# bldc_driver.net
KiCad netlist of a schematic drawn in EAGLE
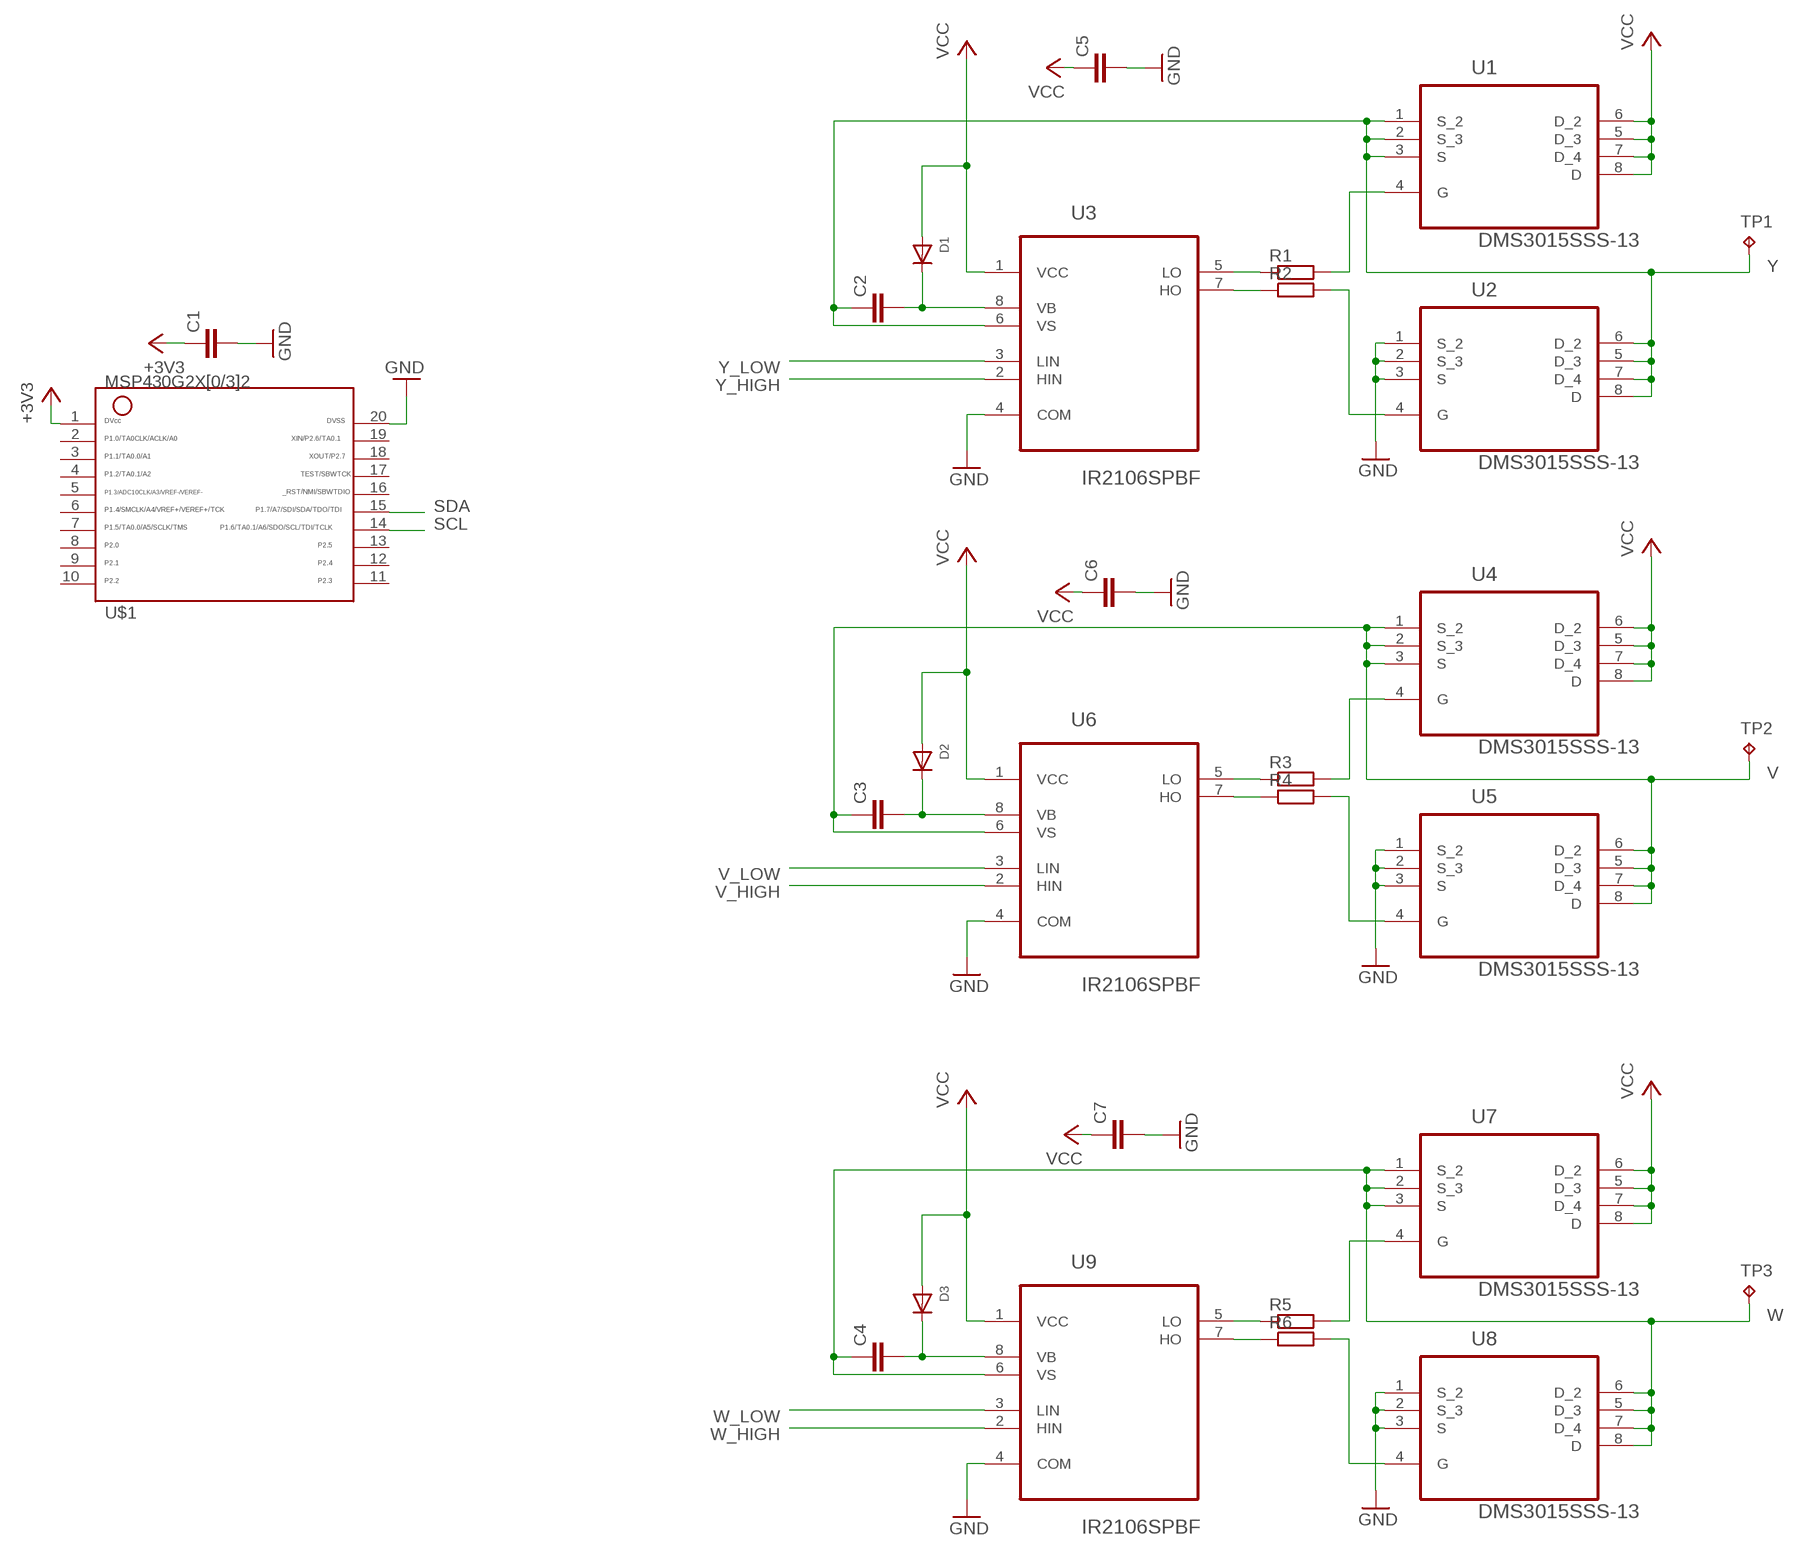
[diagram p0: schematic, sheet 1]

(export (version "E")
  (design (tool "Eeschema 10.0.6"))
  (components
    (comp (ref "C1")
      (value "C-EUC0805")
      (footprint "eagle-import:C0805")
      (libsource (lib "eagle-import") (part "C-EUC0805"))
    )
    (comp (ref "C2")
      (value "C-EUC0805")
      (footprint "eagle-import:C0805")
      (libsource (lib "eagle-import") (part "C-EUC0805"))
    )
    (comp (ref "C3")
      (value "C-EUC0805")
      (footprint "eagle-import:C0805")
      (libsource (lib "eagle-import") (part "C-EUC0805"))
    )
    (comp (ref "C4")
      (value "C-EUC0805")
      (footprint "eagle-import:C0805")
      (libsource (lib "eagle-import") (part "C-EUC0805"))
    )
    (comp (ref "C5")
      (value "C-EUC0805")
      (footprint "eagle-import:C0805")
      (libsource (lib "eagle-import") (part "C-EUC0805"))
    )
    (comp (ref "C6")
      (value "C-EUC0805")
      (footprint "eagle-import:C0805")
      (libsource (lib "eagle-import") (part "C-EUC0805"))
    )
    (comp (ref "C7")
      (value "C-EUC0805")
      (footprint "eagle-import:C0805")
      (libsource (lib "eagle-import") (part "C-EUC0805"))
    )
    (comp (ref "D1")
      (value "DIODE_SOD-123FL")
      (footprint "eagle-import:SOD-123FL")
      (libsource (lib "eagle-import") (part "DIODE_SOD-123FL"))
    )
    (comp (ref "D2")
      (value "DIODE_SOD-123FL")
      (footprint "eagle-import:SOD-123FL")
      (libsource (lib "eagle-import") (part "DIODE_SOD-123FL"))
    )
    (comp (ref "D3")
      (value "DIODE_SOD-123FL")
      (footprint "eagle-import:SOD-123FL")
      (libsource (lib "eagle-import") (part "DIODE_SOD-123FL"))
    )
    (comp (ref "R1")
      (value "R-EU_M0805")
      (footprint "eagle-import:M0805")
      (libsource (lib "eagle-import") (part "R-EU_M0805"))
    )
    (comp (ref "R2")
      (value "R-EU_M0805")
      (footprint "eagle-import:M0805")
      (libsource (lib "eagle-import") (part "R-EU_M0805"))
    )
    (comp (ref "R3")
      (value "R-EU_M0805")
      (footprint "eagle-import:M0805")
      (libsource (lib "eagle-import") (part "R-EU_M0805"))
    )
    (comp (ref "R4")
      (value "R-EU_M0805")
      (footprint "eagle-import:M0805")
      (libsource (lib "eagle-import") (part "R-EU_M0805"))
    )
    (comp (ref "R5")
      (value "R-EU_M0805")
      (footprint "eagle-import:M0805")
      (libsource (lib "eagle-import") (part "R-EU_M0805"))
    )
    (comp (ref "R6")
      (value "R-EU_M0805")
      (footprint "eagle-import:M0805")
      (libsource (lib "eagle-import") (part "R-EU_M0805"))
    )
    (comp (ref "TP1")
      (value "TPTP18R")
      (footprint "eagle-import:TP18R")
      (libsource (lib "eagle-import") (part "TPTP18R"))
    )
    (comp (ref "TP2")
      (value "TPTP18R")
      (footprint "eagle-import:TP18R")
      (libsource (lib "eagle-import") (part "TPTP18R"))
    )
    (comp (ref "TP3")
      (value "TPTP18R")
      (footprint "eagle-import:TP18R")
      (libsource (lib "eagle-import") (part "TPTP18R"))
    )
    (comp (ref "U$1")
      (value "G2X[0/3]2---PW20")
      (footprint "eagle-import:PW20")
      (libsource (lib "eagle-import") (part "G2X[0/3]2---PW20"))
    )
    (comp (ref "U1")
      (value "DMS3015SSS-13")
      (footprint "eagle-import:SOIC127P600X175-8N")
      (libsource (lib "eagle-import") (part "DMS3015SSS-13"))
    )
    (comp (ref "U2")
      (value "DMS3015SSS-13")
      (footprint "eagle-import:SOIC127P600X175-8N")
      (libsource (lib "eagle-import") (part "DMS3015SSS-13"))
    )
    (comp (ref "U3")
      (value "IR2106SPBF")
      (footprint "eagle-import:SOIC127P600X175-8N")
      (libsource (lib "eagle-import") (part "IR2106SPBF"))
    )
    (comp (ref "U4")
      (value "DMS3015SSS-13")
      (footprint "eagle-import:SOIC127P600X175-8N")
      (libsource (lib "eagle-import") (part "DMS3015SSS-13"))
    )
    (comp (ref "U5")
      (value "DMS3015SSS-13")
      (footprint "eagle-import:SOIC127P600X175-8N")
      (libsource (lib "eagle-import") (part "DMS3015SSS-13"))
    )
    (comp (ref "U6")
      (value "IR2106SPBF")
      (footprint "eagle-import:SOIC127P600X175-8N")
      (libsource (lib "eagle-import") (part "IR2106SPBF"))
    )
    (comp (ref "U7")
      (value "DMS3015SSS-13")
      (footprint "eagle-import:SOIC127P600X175-8N")
      (libsource (lib "eagle-import") (part "DMS3015SSS-13"))
    )
    (comp (ref "U8")
      (value "DMS3015SSS-13")
      (footprint "eagle-import:SOIC127P600X175-8N")
      (libsource (lib "eagle-import") (part "DMS3015SSS-13"))
    )
    (comp (ref "U9")
      (value "IR2106SPBF")
      (footprint "eagle-import:SOIC127P600X175-8N")
      (libsource (lib "eagle-import") (part "IR2106SPBF"))
    )
  )
  (nets
    (net (code "1") (name "+3V3") (class "Default")
      (node (ref "C1") (pin "1") (pinfunction "1_1") (pintype "passive"))
      (node (ref "U$1") (pin "1") (pinfunction "1_1") (pintype "bidirectional"))
    )
    (net (code "2") (name "/SCL") (class "Default")
      (node (ref "U$1") (pin "14") (pinfunction "14_14") (pintype "bidirectional"))
    )
    (net (code "3") (name "/SDA") (class "Default")
      (node (ref "U$1") (pin "15") (pinfunction "15_15") (pintype "bidirectional"))
    )
    (net (code "4") (name "/V") (class "Default")
      (node (ref "C3") (pin "1") (pinfunction "1_1") (pintype "passive"))
      (node (ref "TP2") (pin "TP") (pinfunction "TP_TP") (pintype "input"))
      (node (ref "U4") (pin "1") (pinfunction "S_2_1") (pintype "passive"))
      (node (ref "U4") (pin "2") (pinfunction "S_3_2") (pintype "passive"))
      (node (ref "U4") (pin "3") (pinfunction "S_3") (pintype "passive"))
      (node (ref "U5") (pin "5") (pinfunction "D_3_5") (pintype "passive"))
      (node (ref "U5") (pin "6") (pinfunction "D_2_6") (pintype "passive"))
      (node (ref "U5") (pin "7") (pinfunction "D_4_7") (pintype "passive"))
      (node (ref "U5") (pin "8") (pinfunction "D_8") (pintype "passive"))
      (node (ref "U6") (pin "6") (pinfunction "VS_6") (pintype "power_in"))
    )
    (net (code "5") (name "/V_HIGH") (class "Default")
      (node (ref "U6") (pin "2") (pinfunction "HIN_2") (pintype "input"))
    )
    (net (code "6") (name "/V_LOW") (class "Default")
      (node (ref "U6") (pin "3") (pinfunction "LIN_3") (pintype "input"))
    )
    (net (code "7") (name "/W") (class "Default")
      (node (ref "C4") (pin "1") (pinfunction "1_1") (pintype "passive"))
      (node (ref "TP3") (pin "TP") (pinfunction "TP_TP") (pintype "input"))
      (node (ref "U7") (pin "1") (pinfunction "S_2_1") (pintype "passive"))
      (node (ref "U7") (pin "2") (pinfunction "S_3_2") (pintype "passive"))
      (node (ref "U7") (pin "3") (pinfunction "S_3") (pintype "passive"))
      (node (ref "U8") (pin "5") (pinfunction "D_3_5") (pintype "passive"))
      (node (ref "U8") (pin "6") (pinfunction "D_2_6") (pintype "passive"))
      (node (ref "U8") (pin "7") (pinfunction "D_4_7") (pintype "passive"))
      (node (ref "U8") (pin "8") (pinfunction "D_8") (pintype "passive"))
      (node (ref "U9") (pin "6") (pinfunction "VS_6") (pintype "power_in"))
    )
    (net (code "8") (name "/W_HIGH") (class "Default")
      (node (ref "U9") (pin "2") (pinfunction "HIN_2") (pintype "input"))
    )
    (net (code "9") (name "/W_LOW") (class "Default")
      (node (ref "U9") (pin "3") (pinfunction "LIN_3") (pintype "input"))
    )
    (net (code "10") (name "/Y") (class "Default")
      (node (ref "C2") (pin "1") (pinfunction "1_1") (pintype "passive"))
      (node (ref "TP1") (pin "TP") (pinfunction "TP_TP") (pintype "input"))
      (node (ref "U1") (pin "1") (pinfunction "S_2_1") (pintype "passive"))
      (node (ref "U1") (pin "2") (pinfunction "S_3_2") (pintype "passive"))
      (node (ref "U1") (pin "3") (pinfunction "S_3") (pintype "passive"))
      (node (ref "U2") (pin "5") (pinfunction "D_3_5") (pintype "passive"))
      (node (ref "U2") (pin "6") (pinfunction "D_2_6") (pintype "passive"))
      (node (ref "U2") (pin "7") (pinfunction "D_4_7") (pintype "passive"))
      (node (ref "U2") (pin "8") (pinfunction "D_8") (pintype "passive"))
      (node (ref "U3") (pin "6") (pinfunction "VS_6") (pintype "power_in"))
    )
    (net (code "11") (name "/Y_HIGH") (class "Default")
      (node (ref "U3") (pin "2") (pinfunction "HIN_2") (pintype "input"))
    )
    (net (code "12") (name "/Y_LOW") (class "Default")
      (node (ref "U3") (pin "3") (pinfunction "LIN_3") (pintype "input"))
    )
    (net (code "13") (name "GND") (class "Default")
      (node (ref "C1") (pin "2") (pinfunction "2_2") (pintype "passive"))
      (node (ref "C5") (pin "2") (pinfunction "2_2") (pintype "passive"))
      (node (ref "C6") (pin "2") (pinfunction "2_2") (pintype "passive"))
      (node (ref "C7") (pin "2") (pinfunction "2_2") (pintype "passive"))
      (node (ref "U$1") (pin "20") (pinfunction "20_20") (pintype "bidirectional"))
      (node (ref "U2") (pin "1") (pinfunction "S_2_1") (pintype "passive"))
      (node (ref "U2") (pin "2") (pinfunction "S_3_2") (pintype "passive"))
      (node (ref "U2") (pin "3") (pinfunction "S_3") (pintype "passive"))
      (node (ref "U3") (pin "4") (pinfunction "COM_4") (pintype "passive"))
      (node (ref "U5") (pin "1") (pinfunction "S_2_1") (pintype "passive"))
      (node (ref "U5") (pin "2") (pinfunction "S_3_2") (pintype "passive"))
      (node (ref "U5") (pin "3") (pinfunction "S_3") (pintype "passive"))
      (node (ref "U6") (pin "4") (pinfunction "COM_4") (pintype "passive"))
      (node (ref "U8") (pin "1") (pinfunction "S_2_1") (pintype "passive"))
      (node (ref "U8") (pin "2") (pinfunction "S_3_2") (pintype "passive"))
      (node (ref "U8") (pin "3") (pinfunction "S_3") (pintype "passive"))
      (node (ref "U9") (pin "4") (pinfunction "COM_4") (pintype "passive"))
    )
    (net (code "14") (name "Net-(U1-G)") (class "Default")
      (node (ref "R1") (pin "2") (pinfunction "2_2") (pintype "passive"))
      (node (ref "U1") (pin "4") (pinfunction "G_4") (pintype "passive"))
    )
    (net (code "15") (name "Net-(U2-G)") (class "Default")
      (node (ref "R2") (pin "2") (pinfunction "2_2") (pintype "passive"))
      (node (ref "U2") (pin "4") (pinfunction "G_4") (pintype "passive"))
    )
    (net (code "16") (name "Net-(U3-HO)") (class "Default")
      (node (ref "R2") (pin "1") (pinfunction "1_1") (pintype "passive"))
      (node (ref "U3") (pin "7") (pinfunction "HO_7") (pintype "output"))
    )
    (net (code "17") (name "Net-(U3-LO)") (class "Default")
      (node (ref "R1") (pin "1") (pinfunction "1_1") (pintype "passive"))
      (node (ref "U3") (pin "5") (pinfunction "LO_5") (pintype "output"))
    )
    (net (code "18") (name "Net-(U3-VB)") (class "Default")
      (node (ref "C2") (pin "2") (pinfunction "2_2") (pintype "passive"))
      (node (ref "D1") (pin "C") (pinfunction "C_C") (pintype "passive"))
      (node (ref "U3") (pin "8") (pinfunction "VB_8") (pintype "power_in"))
    )
    (net (code "19") (name "Net-(U4-G)") (class "Default")
      (node (ref "R3") (pin "2") (pinfunction "2_2") (pintype "passive"))
      (node (ref "U4") (pin "4") (pinfunction "G_4") (pintype "passive"))
    )
    (net (code "20") (name "Net-(U5-G)") (class "Default")
      (node (ref "R4") (pin "2") (pinfunction "2_2") (pintype "passive"))
      (node (ref "U5") (pin "4") (pinfunction "G_4") (pintype "passive"))
    )
    (net (code "21") (name "Net-(U6-HO)") (class "Default")
      (node (ref "R4") (pin "1") (pinfunction "1_1") (pintype "passive"))
      (node (ref "U6") (pin "7") (pinfunction "HO_7") (pintype "output"))
    )
    (net (code "22") (name "Net-(U6-LO)") (class "Default")
      (node (ref "R3") (pin "1") (pinfunction "1_1") (pintype "passive"))
      (node (ref "U6") (pin "5") (pinfunction "LO_5") (pintype "output"))
    )
    (net (code "23") (name "Net-(U6-VB)") (class "Default")
      (node (ref "C3") (pin "2") (pinfunction "2_2") (pintype "passive"))
      (node (ref "D2") (pin "C") (pinfunction "C_C") (pintype "passive"))
      (node (ref "U6") (pin "8") (pinfunction "VB_8") (pintype "power_in"))
    )
    (net (code "24") (name "Net-(U7-G)") (class "Default")
      (node (ref "R5") (pin "2") (pinfunction "2_2") (pintype "passive"))
      (node (ref "U7") (pin "4") (pinfunction "G_4") (pintype "passive"))
    )
    (net (code "25") (name "Net-(U8-G)") (class "Default")
      (node (ref "R6") (pin "2") (pinfunction "2_2") (pintype "passive"))
      (node (ref "U8") (pin "4") (pinfunction "G_4") (pintype "passive"))
    )
    (net (code "26") (name "Net-(U9-HO)") (class "Default")
      (node (ref "R6") (pin "1") (pinfunction "1_1") (pintype "passive"))
      (node (ref "U9") (pin "7") (pinfunction "HO_7") (pintype "output"))
    )
    (net (code "27") (name "Net-(U9-LO)") (class "Default")
      (node (ref "R5") (pin "1") (pinfunction "1_1") (pintype "passive"))
      (node (ref "U9") (pin "5") (pinfunction "LO_5") (pintype "output"))
    )
    (net (code "28") (name "Net-(U9-VB)") (class "Default")
      (node (ref "C4") (pin "2") (pinfunction "2_2") (pintype "passive"))
      (node (ref "D3") (pin "C") (pinfunction "C_C") (pintype "passive"))
      (node (ref "U9") (pin "8") (pinfunction "VB_8") (pintype "power_in"))
    )
    (net (code "29") (name "VCC") (class "Default")
      (node (ref "C5") (pin "1") (pinfunction "1_1") (pintype "passive"))
      (node (ref "C6") (pin "1") (pinfunction "1_1") (pintype "passive"))
      (node (ref "C7") (pin "1") (pinfunction "1_1") (pintype "passive"))
      (node (ref "D1") (pin "A") (pinfunction "A_A") (pintype "passive"))
      (node (ref "D2") (pin "A") (pinfunction "A_A") (pintype "passive"))
      (node (ref "D3") (pin "A") (pinfunction "A_A") (pintype "passive"))
      (node (ref "U1") (pin "5") (pinfunction "D_3_5") (pintype "passive"))
      (node (ref "U1") (pin "6") (pinfunction "D_2_6") (pintype "passive"))
      (node (ref "U1") (pin "7") (pinfunction "D_4_7") (pintype "passive"))
      (node (ref "U1") (pin "8") (pinfunction "D_8") (pintype "passive"))
      (node (ref "U3") (pin "1") (pinfunction "VCC_1") (pintype "power_in"))
      (node (ref "U4") (pin "5") (pinfunction "D_3_5") (pintype "passive"))
      (node (ref "U4") (pin "6") (pinfunction "D_2_6") (pintype "passive"))
      (node (ref "U4") (pin "7") (pinfunction "D_4_7") (pintype "passive"))
      (node (ref "U4") (pin "8") (pinfunction "D_8") (pintype "passive"))
      (node (ref "U6") (pin "1") (pinfunction "VCC_1") (pintype "power_in"))
      (node (ref "U7") (pin "5") (pinfunction "D_3_5") (pintype "passive"))
      (node (ref "U7") (pin "6") (pinfunction "D_2_6") (pintype "passive"))
      (node (ref "U7") (pin "7") (pinfunction "D_4_7") (pintype "passive"))
      (node (ref "U7") (pin "8") (pinfunction "D_8") (pintype "passive"))
      (node (ref "U9") (pin "1") (pinfunction "VCC_1") (pintype "power_in"))
    )
    (net (code "30") (name "unconnected-(U$1-Pad2)") (class "Default")
      (node (ref "U$1") (pin "2") (pinfunction "2_2") (pintype "bidirectional"))
    )
    (net (code "31") (name "unconnected-(U$1-Pad3)") (class "Default")
      (node (ref "U$1") (pin "3") (pinfunction "3_3") (pintype "bidirectional"))
    )
    (net (code "32") (name "unconnected-(U$1-Pad4)") (class "Default")
      (node (ref "U$1") (pin "4") (pinfunction "4_4") (pintype "bidirectional"))
    )
    (net (code "33") (name "unconnected-(U$1-Pad5)") (class "Default")
      (node (ref "U$1") (pin "5") (pinfunction "5_5") (pintype "bidirectional"))
    )
    (net (code "34") (name "unconnected-(U$1-Pad6)") (class "Default")
      (node (ref "U$1") (pin "6") (pinfunction "6_6") (pintype "bidirectional"))
    )
    (net (code "35") (name "unconnected-(U$1-Pad7)") (class "Default")
      (node (ref "U$1") (pin "7") (pinfunction "7_7") (pintype "bidirectional"))
    )
    (net (code "36") (name "unconnected-(U$1-Pad8)") (class "Default")
      (node (ref "U$1") (pin "8") (pinfunction "8_8") (pintype "bidirectional"))
    )
    (net (code "37") (name "unconnected-(U$1-Pad9)") (class "Default")
      (node (ref "U$1") (pin "9") (pinfunction "9_9") (pintype "bidirectional"))
    )
    (net (code "38") (name "unconnected-(U$1-Pad10)") (class "Default")
      (node (ref "U$1") (pin "10") (pinfunction "10_10") (pintype "bidirectional"))
    )
    (net (code "39") (name "unconnected-(U$1-Pad11)") (class "Default")
      (node (ref "U$1") (pin "11") (pinfunction "11_11") (pintype "bidirectional"))
    )
    (net (code "40") (name "unconnected-(U$1-Pad12)") (class "Default")
      (node (ref "U$1") (pin "12") (pinfunction "12_12") (pintype "bidirectional"))
    )
    (net (code "41") (name "unconnected-(U$1-Pad13)") (class "Default")
      (node (ref "U$1") (pin "13") (pinfunction "13_13") (pintype "bidirectional"))
    )
    (net (code "42") (name "unconnected-(U$1-Pad16)") (class "Default")
      (node (ref "U$1") (pin "16") (pinfunction "16_16") (pintype "bidirectional"))
    )
    (net (code "43") (name "unconnected-(U$1-Pad17)") (class "Default")
      (node (ref "U$1") (pin "17") (pinfunction "17_17") (pintype "bidirectional"))
    )
    (net (code "44") (name "unconnected-(U$1-Pad18)") (class "Default")
      (node (ref "U$1") (pin "18") (pinfunction "18_18") (pintype "bidirectional"))
    )
    (net (code "45") (name "unconnected-(U$1-Pad19)") (class "Default")
      (node (ref "U$1") (pin "19") (pinfunction "19_19") (pintype "bidirectional"))
    )
  )
)
